# 7V_5V_3V3_Bucks.net
KiCad netlist of a schematic drawn in Altium Designer
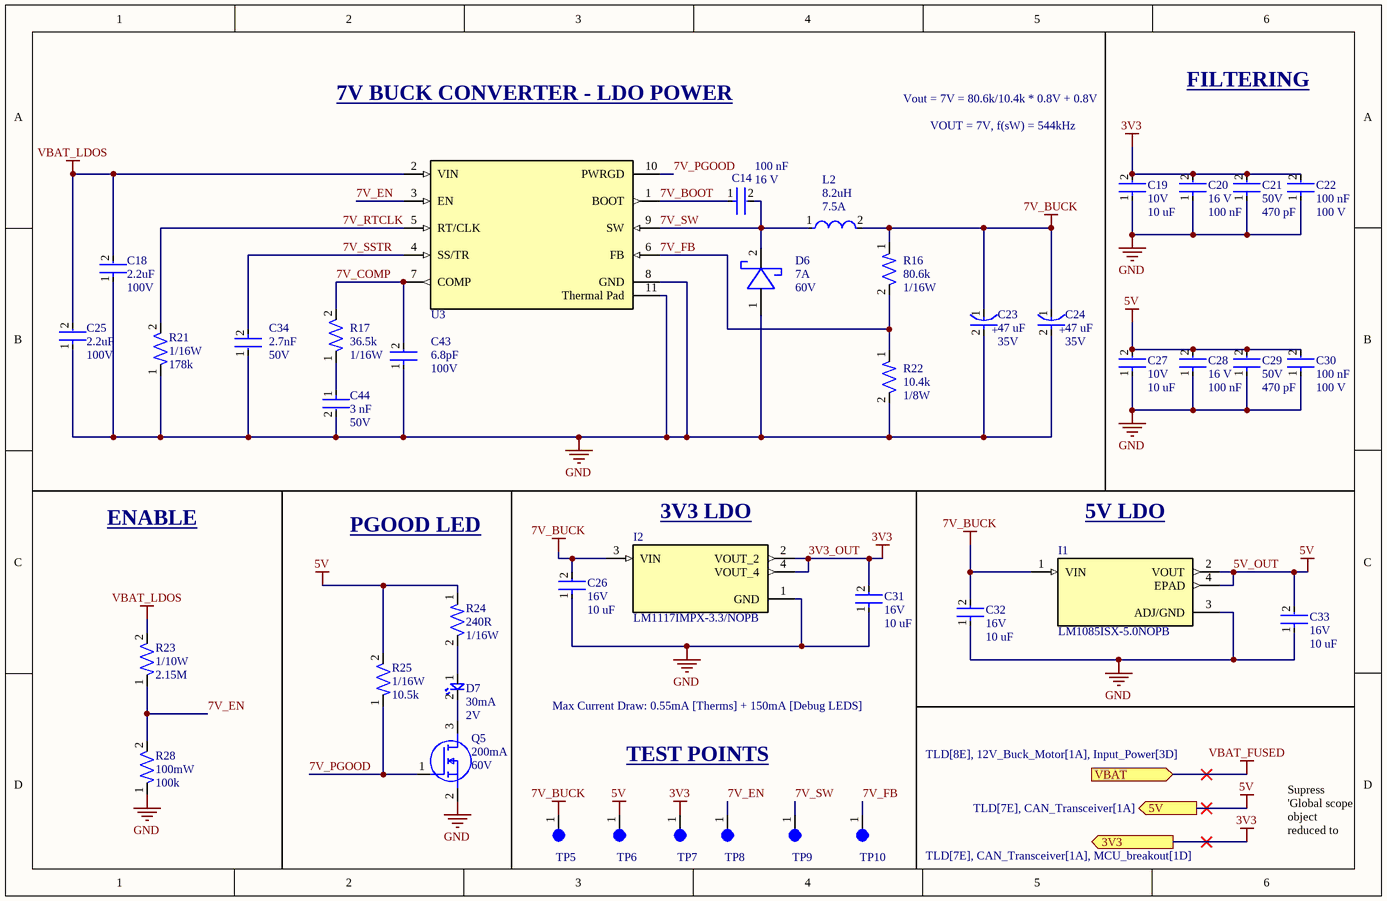
[diagram p0: 7V_5V_3V3_Bucks.SchDoc]

(export (version "E")
  (design (tool "Eeschema 10.0.6"))
  (components
    (comp (ref "C14")
      (value "CC0402KRX7R7BB104")
      (footprint "CAP-0402")
      (description "CAP CER 0.1UF 16V X7R 0402")
      (fields (field (name "VOLTAGE RATING") "16 V") (field (name "CAPACITANCE") "100 nF"))
      (libsource (lib "JLC_25") (part "CAP-0.1U-0001"))
    )
    (comp (ref "C18")
      (value "CC1206KKX7R0BB225")
      (footprint "CAP-1206")
      (description "CAP CER 2.2UF 100V X7R 1206")
      (fields (field (name "CAPACITANCE") "2.2uF") (field (name "VOLTAGE") "100V"))
      (libsource (lib "JLC_25") (part "CAP-2.2U-0001"))
    )
    (comp (ref "C19")
      (value "CC0603KRX5R6BB106")
      (footprint "CAP-0603")
      (description "CAP CER 10UF 10V X5R 0603")
      (fields (field (name "VOLTAGE") "10V") (field (name "CAPACITANCE") "10 uF"))
      (libsource (lib "JLC_25") (part "CAP-10U-0001"))
    )
    (comp (ref "C20")
      (value "CC0402KRX7R7BB104")
      (footprint "CAP-0402")
      (description "CAP CER 0.1UF 16V X7R 0402")
      (fields (field (name "VOLTAGE RATING") "16 V") (field (name "CAPACITANCE") "100 nF"))
      (libsource (lib "JLC_25") (part "CAP-0.1U-0001"))
    )
    (comp (ref "C21")
      (value "CC0805JRNPO9BN471")
      (footprint "CAP-0805")
      (description "CAP CER 470PF 50V C0G/NPO 0805")
      (fields (field (name "VOLTAGE") "50V") (field (name "CAPACITANCE") "470 pF"))
      (libsource (lib "JLC_25") (part "CAP-470P-0001"))
    )
    (comp (ref "C22")
      (value "CC0603KRX7R0BB104")
      (footprint "CAP-0603")
      (description "CAP CER 0.1UF 100V X7R 0603")
      (fields (field (name "CAPACITANCE") "100 nF") (field (name "VOLTAGE") "100 V"))
      (libsource (lib "JLC_25") (part "CAP-100N-0001"))
    )
    (comp (ref "C23")
      (value "EEH-ZC1V470P")
      (footprint "CAP-Radial-SMD")
      (description "CAP ALUM HYBRID 47UF 20% 35V SMD")
      (fields (field (name "CAPACITANCE") "47 uF") (field (name "VOLTAGE") "35V"))
      (libsource (lib "JLC_25") (part "CAP-47U-0002"))
    )
    (comp (ref "C24")
      (value "EEH-ZC1V470P")
      (footprint "CAP-Radial-SMD")
      (description "CAP ALUM HYBRID 47UF 20% 35V SMD")
      (fields (field (name "CAPACITANCE") "47 uF") (field (name "VOLTAGE") "35V"))
      (libsource (lib "JLC_25") (part "CAP-47U-0002"))
    )
    (comp (ref "C25")
      (value "CC1206KKX7R0BB225")
      (footprint "CAP-1206")
      (description "CAP CER 2.2UF 100V X7R 1206")
      (fields (field (name "CAPACITANCE") "2.2uF") (field (name "VOLTAGE") "100V"))
      (libsource (lib "JLC_25") (part "CAP-2.2U-0001"))
    )
    (comp (ref "C26")
      (value "293D106X9016A2TE3")
      (footprint "CAP-1210")
      (description "CAP TANT 10UF 10% 16V 1206")
      (fields (field (name "VOLTAGE") "16V") (field (name "CAPACITANCE") "10 uF"))
      (libsource (lib "JLC_25") (part "CAP-10U-0003_1"))
    )
    (comp (ref "C27")
      (value "CC0603KRX5R6BB106")
      (footprint "CAP-0603")
      (description "CAP CER 10UF 10V X5R 0603")
      (fields (field (name "VOLTAGE") "10V") (field (name "CAPACITANCE") "10 uF"))
      (libsource (lib "JLC_25") (part "CAP-10U-0001"))
    )
    (comp (ref "C28")
      (value "CC0402KRX7R7BB104")
      (footprint "CAP-0402")
      (description "CAP CER 0.1UF 16V X7R 0402")
      (fields (field (name "VOLTAGE RATING") "16 V") (field (name "CAPACITANCE") "100 nF"))
      (libsource (lib "JLC_25") (part "CAP-0.1U-0001"))
    )
    (comp (ref "C29")
      (value "CC0805JRNPO9BN471")
      (footprint "CAP-0805")
      (description "CAP CER 470PF 50V C0G/NPO 0805")
      (fields (field (name "VOLTAGE") "50V") (field (name "CAPACITANCE") "470 pF"))
      (libsource (lib "JLC_25") (part "CAP-470P-0001"))
    )
    (comp (ref "C30")
      (value "CC0603KRX7R0BB104")
      (footprint "CAP-0603")
      (description "CAP CER 0.1UF 100V X7R 0603")
      (fields (field (name "CAPACITANCE") "100 nF") (field (name "VOLTAGE") "100 V"))
      (libsource (lib "JLC_25") (part "CAP-100N-0001"))
    )
    (comp (ref "C31")
      (value "293D106X9016A2TE3")
      (footprint "CAP-1210")
      (description "CAP TANT 10UF 10% 16V 1206")
      (fields (field (name "VOLTAGE") "16V") (field (name "CAPACITANCE") "10 uF"))
      (libsource (lib "JLC_25") (part "CAP-10U-0003_1"))
    )
    (comp (ref "C32")
      (value "293D106X9016A2TE3")
      (footprint "CAP-1210")
      (description "CAP TANT 10UF 10% 16V 1206")
      (fields (field (name "VOLTAGE") "16V") (field (name "CAPACITANCE") "10 uF"))
      (libsource (lib "JLC_25") (part "CAP-10U-0003_1"))
    )
    (comp (ref "C33")
      (value "293D106X9016A2TE3")
      (footprint "CAP-1210")
      (description "CAP TANT 10UF 10% 16V 1206")
      (fields (field (name "VOLTAGE") "16V") (field (name "CAPACITANCE") "10 uF"))
      (libsource (lib "JLC_25") (part "CAP-10U-0003_1"))
    )
    (comp (ref "C34")
      (value "GRM2165C1H272JA01D")
      (footprint "CAP-0805")
      (description "CAP CER 2700PF 50V C0G/NP0 0805")
      (fields (field (name "VOLTAGE") "50V") (field (name "CAPACITANCE") "2.7nF"))
      (libsource (lib "JLC_25") (part "CAP-2.7N-0001"))
    )
    (comp (ref "C43")
      (value "CC0603CRNPO0BN6R8")
      (footprint "CAP-0603")
      (description "CAP CER 6.8PF 100V C0G/NPO 0603")
      (fields (field (name "VOLTAGE") "100V") (field (name "CAPACITANCE") "6.8pF"))
      (libsource (lib "JLC_25") (part "CAP-6.8P-0001"))
    )
    (comp (ref "C44")
      (value "GRM1885C1H302JA01D")
      (footprint "CAP-0603")
      (description "3000 pF ±5% 50V Ceramic Capacitor C0G, NP0 0603 (1608 Metric)")
      (fields (field (name "VOLTAGE") "50V") (field (name "CAPACITANCE") "3 nF"))
      (libsource (lib "JLC_25") (part "CAP-3N-0001"))
    )
    (comp (ref "D6")
      (value "PDS760-13")
      (footprint "DO-POWERDI5")
      (description "DIODE SCHOTTKY 60V 7A POWERDI5")
      (fields (field (name "FORWARD CURRENT") "7A") (field (name "REVERSE VOLTAGE (DC)") "60V"))
      (libsource (lib "JLC_25") (part "DIO-SCHOTTKY-0001"))
    )
    (comp (ref "D7")
      (value "BL-HKC36G-AV-TRB")
      (footprint "LED-0603")
      (description "LED YELLOW CLEAR 0603 SMD")
      (fields (field (name "FORWARD CURRENT") "30mA") (field (name "FORWARD VOLTAGE") "2V"))
      (libsource (lib "JLC_25") (part "LED-0001"))
    )
    (comp (ref "I1")
      (value "LM1085ISX-5.0NOPB")
      (footprint "IC-TO-263-4")
      (description "IC REG LIN 5V 3A DDPAK/TO263-3")
      (libsource (lib "JLC_25") (part "IC_LDO_5V_0002"))
    )
    (comp (ref "I2")
      (value "LM1117IMPX-3.3/NOPB")
      (footprint "IC-SOT-223-4")
      (description "IC REG LIN 3.3V 800MA SOT223-4")
      (libsource (lib "JLC_25") (part "IC_LDO_3V3_0001"))
    )
    (comp (ref "L2")
      (value "IHLP2525CZER8R2M01")
      (footprint "IND25X25CZ")
      (description "8.2 µH Shielded Molded Inductor 4 A 68mOhm Max Nonstandard")
      (fields (field (name "INDUCTANCE") "8.2uH") (field (name "CURRENT RATING") "7.5A"))
      (libsource (lib "JLC_25") (part "IND-8.2U-0001"))
    )
    (comp (ref "Q5")
      (value "T2N7002AK,LM")
      (footprint "IC-SOT23-3")
      (description "MOSFET N-CH 60V 200MA SOT23")
      (fields (field (name "CONTINUOUS CURRENT") "200mA") (field (name "VOLTAGE") "60V"))
      (libsource (lib "JLC_25") (part "NMOS-200MA-0001"))
    )
    (comp (ref "R16")
      (value "RC0402FR-0780K6L")
      (footprint "RES-0402")
      (description "80.6 kOhms ±1% 0.063W, 1/16W Chip Resistor 0402 (1005 Metric) Moisture Resistant Thick Film")
      (fields
        (field (name "TOLERANCE") "1%")
        (field (name "RESISTANCE") "80.6k")
        (field (name "POWER") "1/16W")
      )
      (libsource (lib "JLC_25") (part "RES-80.6k-0001"))
    )
    (comp (ref "R17")
      (value "RC0402FR-0736K5L")
      (footprint "RES-0402")
      (description "36.5 kOhms ±1% 0.063W, 1/16W Chip Resistor 0402 (1005 Metric) Moisture Resistant Thick Film")
      (fields (field (name "POWER") "1/16W") (field (name "RESISTANCE") "36.5k"))
      (libsource (lib "JLC_25") (part "RES-36.5k-0001"))
    )
    (comp (ref "R21")
      (value "RTT021783FTH")
      (footprint "RES-0402")
      (description "62.5mW Thick Film Resistors 50V ±100ppm/℃ ±1% 178kΩ 0402 Chip Resistor - Surface Mount ROHS")
      (fields
        (field (name "TOLERANCE") "1%")
        (field (name "POWER") "1/16W")
        (field (name "RESISTANCE") "178k")
      )
      (libsource (lib "JLC_25") (part "RES-178k-0001_1"))
    )
    (comp (ref "R22")
      (value "RT0805BRD0710K4L")
      (footprint "RES-0805")
      (description "10.4 kOhms ±0.1% 0.125W, 1/8W Chip Resistor 0805 (2012 Metric) Thin Film")
      (fields
        (field (name "TOLERANCE") "1%")
        (field (name "POWER") "1/8W")
        (field (name "RESISTANCE") "10.4k")
      )
      (libsource (lib "JLC_25") (part "RES-10.4k-0001"))
    )
    (comp (ref "R23")
      (value "RC0603FR-072M15L")
      (footprint "RES-0603")
      (description "RES SMD 2.15M OHM 1% 1/10W 0603")
      (fields
        (field (name "TOLERANCE") "1%")
        (field (name "POWER") "1/10W")
        (field (name "RESISTANCE") "2.15M")
      )
      (libsource (lib "JLC_25") (part "RES-2.15M-0001"))
    )
    (comp (ref "R24")
      (value "RC0402FR-07240RL")
      (footprint "RES-0402")
      (description "240R 0.063W 1% 0402 (1005 Metric)  SMD")
      (fields
        (field (name "TOLERANCE") "1%")
        (field (name "RESISTANCE") "240R")
        (field (name "POWER") "1/16W")
      )
      (libsource (lib "JLC_25") (part "RES-240-0001"))
    )
    (comp (ref "R25")
      (value "RC0402FR-0710K5L")
      (footprint "RES-0402")
      (description "RES 10.5K OHM 1% 1/16W 0402")
      (fields
        (field (name "TOLERANCE") "1%")
        (field (name "POWER") "1/16W")
        (field (name "RESISTANCE") "10.5k")
      )
      (libsource (lib "JLC_25") (part "RES-10.5k-0001"))
    )
    (comp (ref "R28")
      (value "RC0603FR-07100KL")
      (footprint "RES-0603")
      (description "RES SMD 100K OHM 1% 1/10W 0603")
      (fields
        (field (name "TOLERANCE") "1%")
        (field (name "POWER") "100mW")
        (field (name "RESISTANCE") "100k")
      )
      (libsource (lib "JLC_25") (part "RES-100k-0001"))
    )
    (comp (ref "TP5")
      (value "5003")
      (footprint "TEST-POINT-0001")
      (description "Oranange PC Test Point, Miniature Phoisphor Bronze Silver Plating Through Hole Mounting Type")
      (libsource (lib "JLC_25") (part "TEST-POINT-0001"))
    )
    (comp (ref "TP6")
      (value "5003")
      (footprint "TEST-POINT-0001")
      (description "Oranange PC Test Point, Miniature Phoisphor Bronze Silver Plating Through Hole Mounting Type")
      (libsource (lib "JLC_25") (part "TEST-POINT-0001"))
    )
    (comp (ref "TP7")
      (value "5003")
      (footprint "TEST-POINT-0001")
      (description "Oranange PC Test Point, Miniature Phoisphor Bronze Silver Plating Through Hole Mounting Type")
      (libsource (lib "JLC_25") (part "TEST-POINT-0001"))
    )
    (comp (ref "TP8")
      (value "5003")
      (footprint "TEST-POINT-0001")
      (description "Oranange PC Test Point, Miniature Phoisphor Bronze Silver Plating Through Hole Mounting Type")
      (libsource (lib "JLC_25") (part "TEST-POINT-0001"))
    )
    (comp (ref "TP9")
      (value "5003")
      (footprint "TEST-POINT-0001")
      (description "Oranange PC Test Point, Miniature Phoisphor Bronze Silver Plating Through Hole Mounting Type")
      (libsource (lib "JLC_25") (part "TEST-POINT-0001"))
    )
    (comp (ref "TP10")
      (value "5003")
      (footprint "TEST-POINT-0001")
      (description "Oranange PC Test Point, Miniature Phoisphor Bronze Silver Plating Through Hole Mounting Type")
      (libsource (lib "JLC_25") (part "TEST-POINT-0001"))
    )
    (comp (ref "U3")
      (value "TPS54561DPRR")
      (footprint "IC-10WSON")
      (description "IC REG BUCK ADJ 5A 10WSON")
      (libsource (lib "JLC_25") (part "IC-BUCK-0001"))
    )
  )
  (nets
    (net (code "1") (name "/7V_BOOT") (class "Default")
      (node (ref "C14") (pin "1") (pinfunction "1_1") (pintype "passive"))
      (node (ref "U3") (pin "1") (pinfunction "BOOT_1") (pintype "output"))
    )
    (net (code "2") (name "/7V_COMP") (class "Default")
      (node (ref "C43") (pin "2") (pinfunction "2_2") (pintype "passive"))
      (node (ref "R17") (pin "2") (pinfunction "2_2") (pintype "passive"))
      (node (ref "U3") (pin "7") (pinfunction "COMP_7") (pintype "output"))
    )
    (net (code "3") (name "/7V_EN") (class "Default")
      (node (ref "R23") (pin "1") (pinfunction "1_1") (pintype "passive"))
      (node (ref "R28") (pin "2") (pinfunction "2_2") (pintype "passive"))
      (node (ref "TP8") (pin "1") (pinfunction "0_1") (pintype "passive"))
      (node (ref "U3") (pin "3") (pinfunction "EN_3") (pintype "input"))
    )
    (net (code "4") (name "/7V_FB") (class "Default")
      (node (ref "R16") (pin "2") (pinfunction "2_2") (pintype "passive"))
      (node (ref "R22") (pin "1") (pinfunction "1_1") (pintype "passive"))
      (node (ref "TP10") (pin "1") (pinfunction "0_1") (pintype "passive"))
      (node (ref "U3") (pin "6") (pinfunction "FB_6") (pintype "input"))
    )
    (net (code "5") (name "/7V_PGOOD") (class "Default")
      (node (ref "Q5") (pin "1") (pinfunction "G_1") (pintype "passive"))
      (node (ref "R25") (pin "1") (pinfunction "1_1") (pintype "passive"))
      (node (ref "U3") (pin "10") (pinfunction "PWRGD_10") (pintype "open_collector"))
    )
    (net (code "6") (name "/7V_RTCLK") (class "Default")
      (node (ref "R21") (pin "2") (pinfunction "2_2") (pintype "passive"))
      (node (ref "U3") (pin "5") (pinfunction "RT/CLK_5") (pintype "input"))
    )
    (net (code "7") (name "/7V_SSTR") (class "Default")
      (node (ref "C34") (pin "2") (pinfunction "2_2") (pintype "passive"))
      (node (ref "U3") (pin "4") (pinfunction "SS/TR_4") (pintype "input"))
    )
    (net (code "8") (name "/7V_SW") (class "Default")
      (node (ref "C14") (pin "2") (pinfunction "2_2") (pintype "passive"))
      (node (ref "D6") (pin "2") (pinfunction "ANODE_2") (pintype "passive"))
      (node (ref "L2") (pin "1") (pinfunction "1_1") (pintype "passive"))
      (node (ref "TP9") (pin "1") (pinfunction "0_1") (pintype "passive"))
      (node (ref "U3") (pin "9") (pinfunction "SW_9") (pintype "input"))
    )
    (net (code "9") (name "3V3") (class "Default")
      (node (ref "C19") (pin "2") (pinfunction "2_2") (pintype "passive"))
      (node (ref "C20") (pin "2") (pinfunction "2_2") (pintype "passive"))
      (node (ref "C21") (pin "2") (pinfunction "2_2") (pintype "passive"))
      (node (ref "C22") (pin "2") (pinfunction "2_2") (pintype "passive"))
      (node (ref "C31") (pin "2") (pinfunction "2_2") (pintype "passive"))
      (node (ref "I2") (pin "2") (pinfunction "VOUT_2_2") (pintype "output"))
      (node (ref "I2") (pin "4") (pinfunction "VOUT_4_4") (pintype "output"))
      (node (ref "TP7") (pin "1") (pinfunction "0_1") (pintype "passive"))
    )
    (net (code "10") (name "5V") (class "Default")
      (node (ref "C27") (pin "2") (pinfunction "2_2") (pintype "passive"))
      (node (ref "C28") (pin "2") (pinfunction "2_2") (pintype "passive"))
      (node (ref "C29") (pin "2") (pinfunction "2_2") (pintype "passive"))
      (node (ref "C30") (pin "2") (pinfunction "2_2") (pintype "passive"))
      (node (ref "C33") (pin "2") (pinfunction "2_2") (pintype "passive"))
      (node (ref "I1") (pin "2") (pinfunction "VOUT_2") (pintype "output"))
      (node (ref "I1") (pin "4") (pinfunction "EPAD_4") (pintype "output"))
      (node (ref "R24") (pin "1") (pinfunction "1_1") (pintype "passive"))
      (node (ref "R25") (pin "2") (pinfunction "2_2") (pintype "passive"))
      (node (ref "TP6") (pin "1") (pinfunction "0_1") (pintype "passive"))
    )
    (net (code "11") (name "7V_BUCK") (class "Default")
      (node (ref "C23") (pin "1") (pinfunction "C_1") (pintype "passive"))
      (node (ref "C24") (pin "1") (pinfunction "C_1") (pintype "passive"))
      (node (ref "C26") (pin "2") (pinfunction "2_2") (pintype "passive"))
      (node (ref "C32") (pin "2") (pinfunction "2_2") (pintype "passive"))
      (node (ref "I1") (pin "1") (pinfunction "VIN_1") (pintype "input"))
      (node (ref "I2") (pin "3") (pinfunction "VIN_3") (pintype "input"))
      (node (ref "L2") (pin "2") (pinfunction "2_2") (pintype "passive"))
      (node (ref "R16") (pin "1") (pinfunction "1_1") (pintype "passive"))
      (node (ref "TP5") (pin "1") (pinfunction "0_1") (pintype "passive"))
    )
    (net (code "12") (name "GND") (class "Default")
      (node (ref "C18") (pin "1") (pinfunction "1_1") (pintype "passive"))
      (node (ref "C19") (pin "1") (pinfunction "1_1") (pintype "passive"))
      (node (ref "C20") (pin "1") (pinfunction "1_1") (pintype "passive"))
      (node (ref "C21") (pin "1") (pinfunction "1_1") (pintype "passive"))
      (node (ref "C22") (pin "1") (pinfunction "1_1") (pintype "passive"))
      (node (ref "C23") (pin "2") (pinfunction "A_2") (pintype "passive"))
      (node (ref "C24") (pin "2") (pinfunction "A_2") (pintype "passive"))
      (node (ref "C25") (pin "1") (pinfunction "1_1") (pintype "passive"))
      (node (ref "C26") (pin "1") (pinfunction "1_1") (pintype "passive"))
      (node (ref "C27") (pin "1") (pinfunction "1_1") (pintype "passive"))
      (node (ref "C28") (pin "1") (pinfunction "1_1") (pintype "passive"))
      (node (ref "C29") (pin "1") (pinfunction "1_1") (pintype "passive"))
      (node (ref "C30") (pin "1") (pinfunction "1_1") (pintype "passive"))
      (node (ref "C31") (pin "1") (pinfunction "1_1") (pintype "passive"))
      (node (ref "C32") (pin "1") (pinfunction "1_1") (pintype "passive"))
      (node (ref "C33") (pin "1") (pinfunction "1_1") (pintype "passive"))
      (node (ref "C34") (pin "1") (pinfunction "1_1") (pintype "passive"))
      (node (ref "C43") (pin "1") (pinfunction "1_1") (pintype "passive"))
      (node (ref "C44") (pin "2") (pinfunction "2_2") (pintype "passive"))
      (node (ref "D6") (pin "1") (pinfunction "CATHODE_1") (pintype "passive"))
      (node (ref "I1") (pin "3") (pinfunction "ADJ/GND_3") (pintype "power_in"))
      (node (ref "I2") (pin "1") (pinfunction "GND_1") (pintype "power_in"))
      (node (ref "Q5") (pin "2") (pinfunction "S_2") (pintype "passive"))
      (node (ref "R21") (pin "1") (pinfunction "1_1") (pintype "passive"))
      (node (ref "R22") (pin "2") (pinfunction "2_2") (pintype "passive"))
      (node (ref "R28") (pin "1") (pinfunction "1_1") (pintype "passive"))
      (node (ref "U3") (pin "11") (pinfunction "Thermal_Pad_11") (pintype "power_in"))
      (node (ref "U3") (pin "8") (pinfunction "GND_8") (pintype "power_in"))
    )
    (net (code "13") (name "Net-(C44-Pad1)") (class "Default")
      (node (ref "C44") (pin "1") (pinfunction "1_1") (pintype "passive"))
      (node (ref "R17") (pin "1") (pinfunction "1_1") (pintype "passive"))
    )
    (net (code "14") (name "Net-(D7-Pad1)") (class "Default")
      (node (ref "D7") (pin "1") (pinfunction "1_1") (pintype "passive"))
      (node (ref "R24") (pin "2") (pinfunction "2_2") (pintype "passive"))
    )
    (net (code "15") (name "Net-(Q5-D)") (class "Default")
      (node (ref "D7") (pin "2") (pinfunction "2_2") (pintype "passive"))
      (node (ref "Q5") (pin "3") (pinfunction "D_3") (pintype "passive"))
    )
    (net (code "17") (name "VBAT_LDOS") (class "Default")
      (node (ref "C18") (pin "2") (pinfunction "2_2") (pintype "passive"))
      (node (ref "C25") (pin "2") (pinfunction "2_2") (pintype "passive"))
      (node (ref "R23") (pin "2") (pinfunction "2_2") (pintype "passive"))
      (node (ref "U3") (pin "2") (pinfunction "VIN_2") (pintype "input"))
    )
  )
)
